# Adapter_WBA.net
KiCad netlist of a schematic drawn in EAGLE
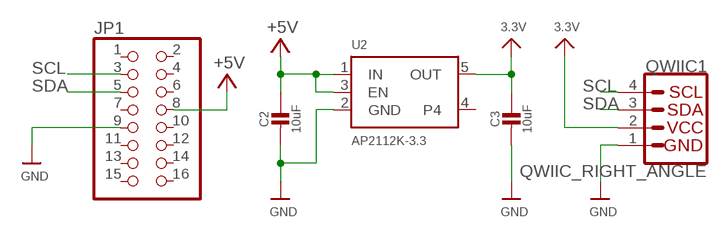
[diagram p0: schematic, sheet 1]

(export (version "E")
  (design (tool "Eeschema 10.0.6"))
  (components
    (comp (ref "C2")
      (value "10uF")
      (footprint "eagle-import:0805-NO")
      (libsource (lib "eagle-import") (part "CAP_CERAMIC0805-NOOUTLINE"))
    )
    (comp (ref "C3")
      (value "10uF")
      (footprint "eagle-import:0805-NO")
      (libsource (lib "eagle-import") (part "CAP_CERAMIC0805-NOOUTLINE"))
    )
    (comp (ref "JP1")
      (value "PINHD-2X8")
      (footprint "eagle-import:2X08")
      (libsource (lib "eagle-import") (part "PINHD-2X8"))
    )
    (comp (ref "QWIIC1")
      (value "QWIIC_RIGHT_ANGLE")
      (footprint "eagle-import:JST04_1MM_RA")
      (libsource (lib "eagle-import") (part "QWIIC_CONNECTORJS-1MM"))
    )
    (comp (ref "U2")
      (value "AP2112K-3.3")
      (footprint "eagle-import:SOT23-5")
      (libsource (lib "eagle-import") (part "VREG_SOT23-5"))
    )
  )
  (nets
    (net (code "1") (name "+5V") (class "Default")
      (node (ref "C2") (pin "1") (pinfunction "1_1") (pintype "passive"))
      (node (ref "JP1") (pin "8") (pinfunction "8_8") (pintype "passive"))
      (node (ref "U2") (pin "1") (pinfunction "IN_1") (pintype "power_in"))
      (node (ref "U2") (pin "3") (pinfunction "EN_3") (pintype "input"))
    )
    (net (code "2") (name "/SCL") (class "Default")
      (node (ref "JP1") (pin "3") (pinfunction "3_3") (pintype "passive"))
      (node (ref "QWIIC1") (pin "4") (pinfunction "4_4") (pintype "passive"))
    )
    (net (code "3") (name "/SDA") (class "Default")
      (node (ref "JP1") (pin "5") (pinfunction "5_5") (pintype "passive"))
      (node (ref "QWIIC1") (pin "3") (pinfunction "3_3") (pintype "passive"))
    )
    (net (code "4") (name "3.3V") (class "Default")
      (node (ref "C3") (pin "1") (pinfunction "1_1") (pintype "passive"))
      (node (ref "QWIIC1") (pin "2") (pinfunction "2_2") (pintype "power_in"))
      (node (ref "U2") (pin "5") (pinfunction "OUT_5") (pintype "power_in"))
    )
    (net (code "5") (name "GND") (class "Default")
      (node (ref "C2") (pin "2") (pinfunction "2_2") (pintype "passive"))
      (node (ref "C3") (pin "2") (pinfunction "2_2") (pintype "passive"))
      (node (ref "JP1") (pin "9") (pinfunction "9_9") (pintype "passive"))
      (node (ref "QWIIC1") (pin "1") (pinfunction "1_1") (pintype "power_in"))
      (node (ref "U2") (pin "2") (pinfunction "GND_2") (pintype "power_in"))
    )
    (net (code "6") (name "unconnected-(JP1-Pad1)") (class "Default")
      (node (ref "JP1") (pin "1") (pinfunction "1_1") (pintype "passive"))
    )
    (net (code "7") (name "unconnected-(JP1-Pad2)") (class "Default")
      (node (ref "JP1") (pin "2") (pinfunction "2_2") (pintype "passive"))
    )
    (net (code "8") (name "unconnected-(JP1-Pad4)") (class "Default")
      (node (ref "JP1") (pin "4") (pinfunction "4_4") (pintype "passive"))
    )
    (net (code "9") (name "unconnected-(JP1-Pad6)") (class "Default")
      (node (ref "JP1") (pin "6") (pinfunction "6_6") (pintype "passive"))
    )
    (net (code "10") (name "unconnected-(JP1-Pad7)") (class "Default")
      (node (ref "JP1") (pin "7") (pinfunction "7_7") (pintype "passive"))
    )
    (net (code "11") (name "unconnected-(JP1-Pad10)") (class "Default")
      (node (ref "JP1") (pin "10") (pinfunction "10_10") (pintype "passive"))
    )
    (net (code "12") (name "unconnected-(JP1-Pad11)") (class "Default")
      (node (ref "JP1") (pin "11") (pinfunction "11_11") (pintype "passive"))
    )
    (net (code "13") (name "unconnected-(JP1-Pad12)") (class "Default")
      (node (ref "JP1") (pin "12") (pinfunction "12_12") (pintype "passive"))
    )
    (net (code "14") (name "unconnected-(JP1-Pad13)") (class "Default")
      (node (ref "JP1") (pin "13") (pinfunction "13_13") (pintype "passive"))
    )
    (net (code "15") (name "unconnected-(JP1-Pad14)") (class "Default")
      (node (ref "JP1") (pin "14") (pinfunction "14_14") (pintype "passive"))
    )
    (net (code "16") (name "unconnected-(JP1-Pad15)") (class "Default")
      (node (ref "JP1") (pin "15") (pinfunction "15_15") (pintype "passive"))
    )
    (net (code "17") (name "unconnected-(JP1-Pad16)") (class "Default")
      (node (ref "JP1") (pin "16") (pinfunction "16_16") (pintype "passive"))
    )
    (net (code "18") (name "unconnected-(U2-P4-Pad4)") (class "Default")
      (node (ref "U2") (pin "4") (pinfunction "P4_4") (pintype "bidirectional"))
    )
  )
)
